# MCU009A_Xds100v2Emu.net
KiCad netlist of a schematic drawn in Altium Designer
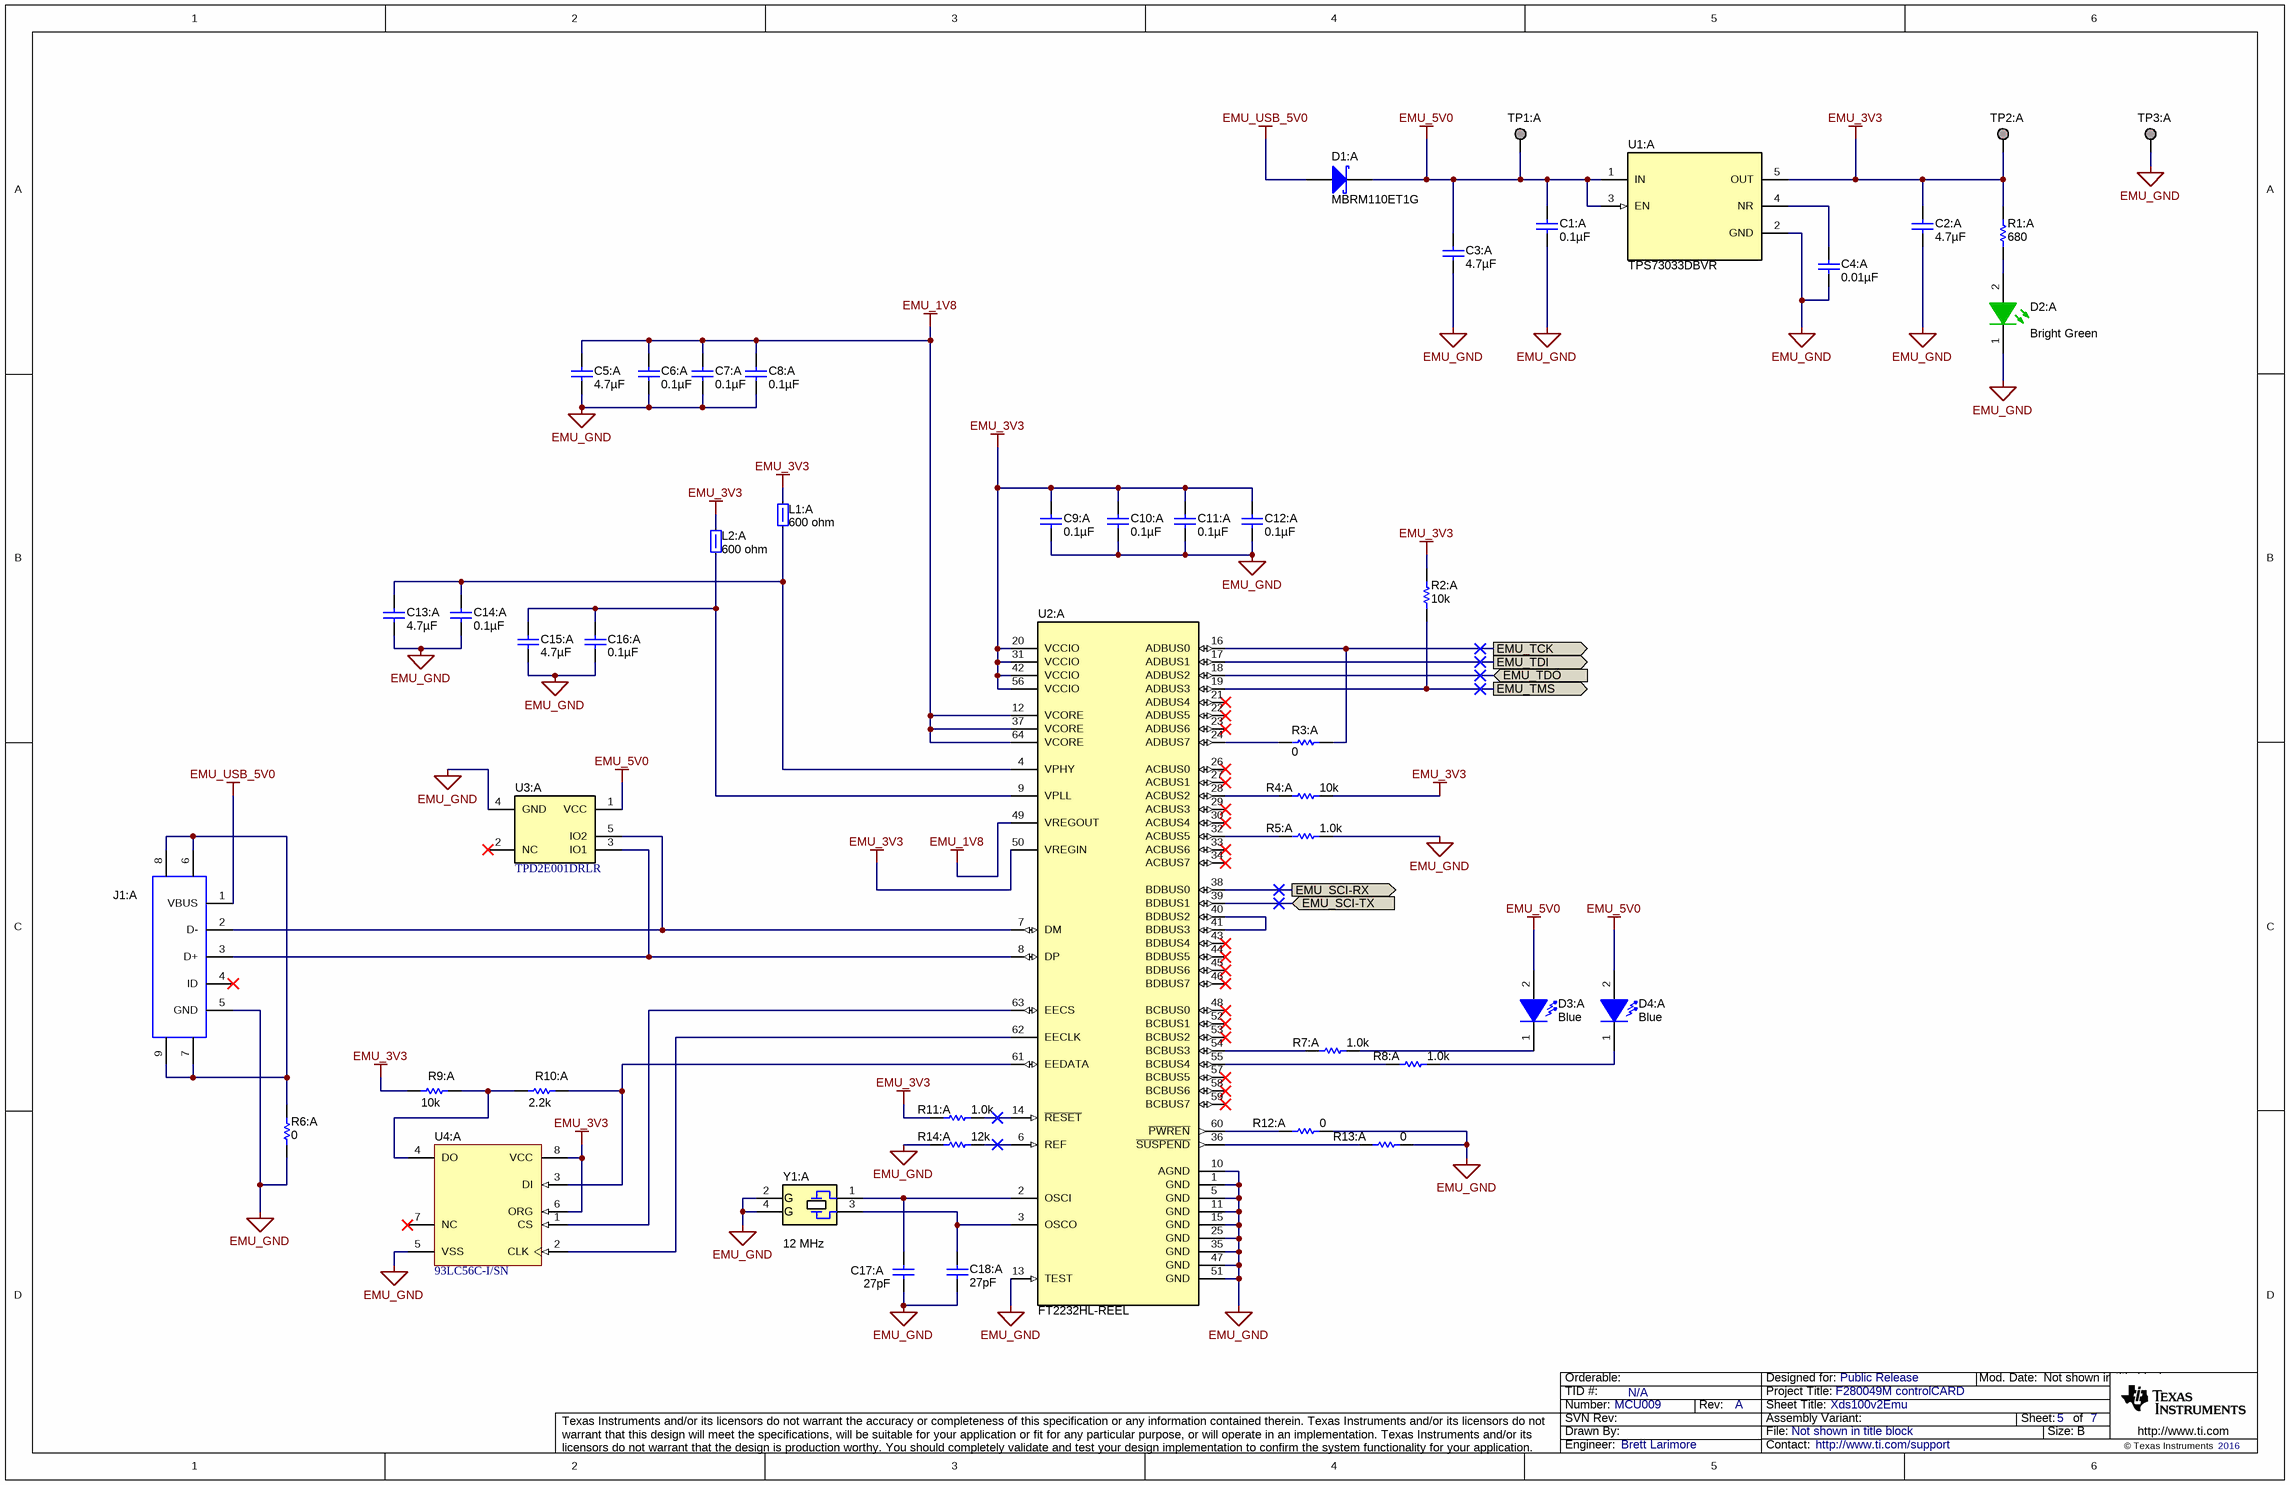
[diagram p0: MCU009A_Xds100v2Emu.SchDoc]

(export (version "E")
  (design (tool "Eeschema 10.0.6"))
  (components
    (comp (ref "C1:A")
      (value "GRM155R71A104KA01D")
      (footprint "0402")
      (description "CAP, CERM, 0.1 µF, 10 V, +/- 10%, X7R, 0402")
      (fields
        (field (name "VALUEDISPLAYED") "0.1µF")
        (field (name "MANUFACTURER") "MuRata")
        (field (name "PUBLISHER") "Texas Instruments")
      )
      (libsource (lib "Capacitor_Ceramic") (part "GRM155R71A104KA01D"))
    )
    (comp (ref "C2:A")
      (value "GRM188R60J475ME19D")
      (footprint "0603")
      (description "CAP, CERM, 4.7 µF, 6.3 V, +/- 20%, X5R, 0603")
      (fields
        (field (name "VALUEDISPLAYED") "4.7µF")
        (field (name "MANUFACTURER") "MuRata")
        (field (name "PUBLISHER") "Texas Instruments")
      )
      (libsource (lib "Capacitor_Ceramic") (part "GRM188R60J475ME19D"))
    )
    (comp (ref "C3:A")
      (value "GRM188R60J475ME19D")
      (footprint "0603")
      (description "CAP, CERM, 4.7 µF, 6.3 V, +/- 20%, X5R, 0603")
      (fields
        (field (name "VALUEDISPLAYED") "4.7µF")
        (field (name "MANUFACTURER") "MuRata")
        (field (name "PUBLISHER") "Texas Instruments")
      )
      (libsource (lib "Capacitor_Ceramic") (part "GRM188R60J475ME19D"))
    )
    (comp (ref "C4:A")
      (value "GRM155R71C103KA01D")
      (footprint "0402")
      (description "CAP, CERM, 0.01 µF, 16 V, +/- 10%, X7R, 0402")
      (fields
        (field (name "VALUEDISPLAYED") "0.01µF")
        (field (name "MANUFACTURER") "MuRata")
        (field (name "PUBLISHER") "Texas Instruments")
      )
      (libsource (lib "Capacitor_Ceramic") (part "GRM155R71C103KA01D"))
    )
    (comp (ref "C5:A")
      (value "GRM188R60J475ME19D")
      (footprint "0603")
      (description "CAP, CERM, 4.7 µF, 6.3 V, +/- 20%, X5R, 0603")
      (fields
        (field (name "VALUEDISPLAYED") "4.7µF")
        (field (name "MANUFACTURER") "MuRata")
        (field (name "PUBLISHER") "Texas Instruments")
      )
      (libsource (lib "Capacitor_Ceramic") (part "GRM188R60J475ME19D"))
    )
    (comp (ref "C6:A")
      (value "GRM155R71A104KA01D")
      (footprint "0402")
      (description "CAP, CERM, 0.1 µF, 10 V, +/- 10%, X7R, 0402")
      (fields
        (field (name "VALUEDISPLAYED") "0.1µF")
        (field (name "MANUFACTURER") "MuRata")
        (field (name "PUBLISHER") "Texas Instruments")
      )
      (libsource (lib "Capacitor_Ceramic") (part "GRM155R71A104KA01D"))
    )
    (comp (ref "C7:A")
      (value "GRM155R71A104KA01D")
      (footprint "0402")
      (description "CAP, CERM, 0.1 µF, 10 V, +/- 10%, X7R, 0402")
      (fields
        (field (name "VALUEDISPLAYED") "0.1µF")
        (field (name "MANUFACTURER") "MuRata")
        (field (name "PUBLISHER") "Texas Instruments")
      )
      (libsource (lib "Capacitor_Ceramic") (part "GRM155R71A104KA01D"))
    )
    (comp (ref "C8:A")
      (value "GRM155R71A104KA01D")
      (footprint "0402")
      (description "CAP, CERM, 0.1 µF, 10 V, +/- 10%, X7R, 0402")
      (fields
        (field (name "VALUEDISPLAYED") "0.1µF")
        (field (name "MANUFACTURER") "MuRata")
        (field (name "PUBLISHER") "Texas Instruments")
      )
      (libsource (lib "Capacitor_Ceramic") (part "GRM155R71A104KA01D"))
    )
    (comp (ref "C9:A")
      (value "GRM155R71A104KA01D")
      (footprint "0402")
      (description "CAP, CERM, 0.1 µF, 10 V, +/- 10%, X7R, 0402")
      (fields
        (field (name "VALUEDISPLAYED") "0.1µF")
        (field (name "MANUFACTURER") "MuRata")
        (field (name "PUBLISHER") "Texas Instruments")
      )
      (libsource (lib "Capacitor_Ceramic") (part "GRM155R71A104KA01D"))
    )
    (comp (ref "C10:A")
      (value "GRM155R71A104KA01D")
      (footprint "0402")
      (description "CAP, CERM, 0.1 µF, 10 V, +/- 10%, X7R, 0402")
      (fields
        (field (name "VALUEDISPLAYED") "0.1µF")
        (field (name "MANUFACTURER") "MuRata")
        (field (name "PUBLISHER") "Texas Instruments")
      )
      (libsource (lib "Capacitor_Ceramic") (part "GRM155R71A104KA01D"))
    )
    (comp (ref "C11:A")
      (value "GRM155R71A104KA01D")
      (footprint "0402")
      (description "CAP, CERM, 0.1 µF, 10 V, +/- 10%, X7R, 0402")
      (fields
        (field (name "VALUEDISPLAYED") "0.1µF")
        (field (name "MANUFACTURER") "MuRata")
        (field (name "PUBLISHER") "Texas Instruments")
      )
      (libsource (lib "Capacitor_Ceramic") (part "GRM155R71A104KA01D"))
    )
    (comp (ref "C12:A")
      (value "GRM155R71A104KA01D")
      (footprint "0402")
      (description "CAP, CERM, 0.1 µF, 10 V, +/- 10%, X7R, 0402")
      (fields
        (field (name "VALUEDISPLAYED") "0.1µF")
        (field (name "MANUFACTURER") "MuRata")
        (field (name "PUBLISHER") "Texas Instruments")
      )
      (libsource (lib "Capacitor_Ceramic") (part "GRM155R71A104KA01D"))
    )
    (comp (ref "C13:A")
      (value "GRM188R60J475ME19D")
      (footprint "0603")
      (description "CAP, CERM, 4.7 µF, 6.3 V, +/- 20%, X5R, 0603")
      (fields
        (field (name "VALUEDISPLAYED") "4.7µF")
        (field (name "MANUFACTURER") "MuRata")
        (field (name "PUBLISHER") "Texas Instruments")
      )
      (libsource (lib "Capacitor_Ceramic") (part "GRM188R60J475ME19D"))
    )
    (comp (ref "C14:A")
      (value "GRM155R71A104KA01D")
      (footprint "0402")
      (description "CAP, CERM, 0.1 µF, 10 V, +/- 10%, X7R, 0402")
      (fields
        (field (name "VALUEDISPLAYED") "0.1µF")
        (field (name "MANUFACTURER") "MuRata")
        (field (name "PUBLISHER") "Texas Instruments")
      )
      (libsource (lib "Capacitor_Ceramic") (part "GRM155R71A104KA01D"))
    )
    (comp (ref "C15:A")
      (value "GRM188R60J475ME19D")
      (footprint "0603")
      (description "CAP, CERM, 4.7 µF, 6.3 V, +/- 20%, X5R, 0603")
      (fields
        (field (name "VALUEDISPLAYED") "4.7µF")
        (field (name "MANUFACTURER") "MuRata")
        (field (name "PUBLISHER") "Texas Instruments")
      )
      (libsource (lib "Capacitor_Ceramic") (part "GRM188R60J475ME19D"))
    )
    (comp (ref "C16:A")
      (value "GRM155R71A104KA01D")
      (footprint "0402")
      (description "CAP, CERM, 0.1 µF, 10 V, +/- 10%, X7R, 0402")
      (fields
        (field (name "VALUEDISPLAYED") "0.1µF")
        (field (name "MANUFACTURER") "MuRata")
        (field (name "PUBLISHER") "Texas Instruments")
      )
      (libsource (lib "Capacitor_Ceramic") (part "GRM155R71A104KA01D"))
    )
    (comp (ref "C17:A")
      (value "GRM1555C1H270JA01D")
      (footprint "0402")
      (description "CAP, CERM, 27 pF, 50 V, +/- 5%, C0G/NP0, 0402")
      (fields
        (field (name "VALUEDISPLAYED") "27pF")
        (field (name "MANUFACTURER") "MuRata")
        (field (name "PUBLISHER") "Texas Instruments")
      )
      (libsource (lib "Capacitor_Ceramic") (part "GRM1555C1H270JA01D"))
    )
    (comp (ref "C18:A")
      (value "GRM1555C1H270JA01D")
      (footprint "0402")
      (description "CAP, CERM, 27 pF, 50 V, +/- 5%, C0G/NP0, 0402")
      (fields
        (field (name "VALUEDISPLAYED") "27pF")
        (field (name "MANUFACTURER") "MuRata")
        (field (name "PUBLISHER") "Texas Instruments")
      )
      (libsource (lib "Capacitor_Ceramic") (part "GRM1555C1H270JA01D"))
    )
    (comp (ref "D1:A")
      (value "MBRM110ET1G")
      (footprint "POWERMITE")
      (description "Diode, Schottky, 10 V, 1 A, AEC-Q101, POWERMITE")
      (fields (field (name "MANUFACTURER") "ON Semiconductor") (field (name "PUBLISHER") "Texas Instruments"))
      (libsource (lib "Diode") (part "MBRM110ET1G"))
    )
    (comp (ref "D2:A")
      (value "Bright Green")
      (footprint "WL-SMCW_Green_0805")
      (description "LED, Bright Green, SMD")
      (fields
        (field (name "PARTNUMBER") "150080VS75000")
        (field (name "MANUFACTURER") "Wurth Elektronik")
        (field (name "SYMBOLCREATOR") "Altium")
        (field (name "PUBLISHER") "Texas Instruments")
      )
      (libsource (lib "LED") (part "150080VS75000"))
    )
    (comp (ref "D3:A")
      (value "Blue")
      (footprint "WL-SMCW_Blue_0805")
      (description "LED, Blue, SMD")
      (fields
        (field (name "MANUFACTURER") "Wurth Elektronik")
        (field (name "PARTNUMBER") "150080BS75000")
        (field (name "PUBLISHER") "Texas Instruments")
      )
      (libsource (lib "LED") (part "150080BS75000"))
    )
    (comp (ref "D4:A")
      (value "Blue")
      (footprint "WL-SMCW_Blue_0805")
      (description "LED, Blue, SMD")
      (fields
        (field (name "MANUFACTURER") "Wurth Elektronik")
        (field (name "PARTNUMBER") "150080BS75000")
        (field (name "PUBLISHER") "Texas Instruments")
      )
      (libsource (lib "LED") (part "150080BS75000"))
    )
    (comp (ref "J1:A")
      (value "65100516121")
      (footprint "Wurth_65100516121")
      (description "Connector, Receptacle, USB Mini B 2.0, SMT")
      (fields
        (field (name "MANUFACTURER") "Wurth Elektronik")
        (field (name "SYMBOLCREATOR") "a0799628")
        (field (name "PUBLISHER") "Texas Instruments")
      )
      (libsource (lib "Connectors_Other") (part "65100516121"))
    )
    (comp (ref "L1:A")
      (value "600 ohm")
      (footprint "0805_HV")
      (description "Ferrite Bead, 600 ohm @ 100 MHz, 0.5 A, 0805")
      (fields
        (field (name "PARTNUMBER") "HZ0805E601R-10")
        (field (name "MANUFACTURER") "Laird-Signal Integrity Products")
        (field (name "PUBLISHER") "Texas Instruments")
      )
      (libsource (lib "FerriteBead") (part "HZ0805E601R-10"))
    )
    (comp (ref "L2:A")
      (value "600 ohm")
      (footprint "0805_HV")
      (description "Ferrite Bead, 600 ohm @ 100 MHz, 0.5 A, 0805")
      (fields
        (field (name "PARTNUMBER") "HZ0805E601R-10")
        (field (name "MANUFACTURER") "Laird-Signal Integrity Products")
        (field (name "PUBLISHER") "Texas Instruments")
      )
      (libsource (lib "FerriteBead") (part "HZ0805E601R-10"))
    )
    (comp (ref "R1:A")
      (value "CRCW0402680RJNED")
      (footprint "0402")
      (description "RES, 680, 5%, 0.063 W, 0402")
      (fields
        (field (name "VALUEDISPLAYED") "680")
        (field (name "MANUFACTURER") "Vishay-Dale")
        (field (name "PUBLISHER") "Texas Instruments")
      )
      (libsource (lib "Resistor_0402") (part "CRCW0402680RJNED"))
    )
    (comp (ref "R2:A")
      (value "CRCW040210K0JNED")
      (footprint "0402")
      (description "RES, 10 k, 5%, 0.063 W, 0402")
      (fields
        (field (name "VALUEDISPLAYED") "10k")
        (field (name "MANUFACTURER") "Vishay-Dale")
        (field (name "PUBLISHER") "Texas Instruments")
      )
      (libsource (lib "Resistor_0402") (part "CRCW040210K0JNED"))
    )
    (comp (ref "R3:A")
      (value "CRCW04020000Z0ED")
      (footprint "0402")
      (description "RES, 0, 5%, 0.063 W, 0402")
      (fields
        (field (name "VALUEDISPLAYED") "0")
        (field (name "MANUFACTURER") "Vishay-Dale")
        (field (name "PUBLISHER") "Texas Instruments")
      )
      (libsource (lib "Resistor_0402") (part "CRCW04020000Z0ED"))
    )
    (comp (ref "R4:A")
      (value "CRCW040210K0JNED")
      (footprint "0402")
      (description "RES, 10 k, 5%, 0.063 W, 0402")
      (fields
        (field (name "VALUEDISPLAYED") "10k")
        (field (name "MANUFACTURER") "Vishay-Dale")
        (field (name "PUBLISHER") "Texas Instruments")
      )
      (libsource (lib "Resistor_0402") (part "CRCW040210K0JNED"))
    )
    (comp (ref "R5:A")
      (value "CRCW04021K00JNED")
      (footprint "0402")
      (description "RES, 1.0 k, 5%, 0.063 W, 0402")
      (fields
        (field (name "VALUEDISPLAYED") "1.0k")
        (field (name "MANUFACTURER") "Vishay-Dale")
        (field (name "PUBLISHER") "Texas Instruments")
      )
      (libsource (lib "Resistor_0402") (part "CRCW04021K00JNED"))
    )
    (comp (ref "R6:A")
      (value "CRCW04020000Z0ED")
      (footprint "0402")
      (description "RES, 0, 5%, 0.063 W, 0402")
      (fields
        (field (name "VALUEDISPLAYED") "0")
        (field (name "MANUFACTURER") "Vishay-Dale")
        (field (name "PUBLISHER") "Texas Instruments")
      )
      (libsource (lib "Resistor_0402") (part "CRCW04020000Z0ED"))
    )
    (comp (ref "R7:A")
      (value "CRCW04021K00JNED")
      (footprint "0402")
      (description "RES, 1.0 k, 5%, 0.063 W, 0402")
      (fields
        (field (name "VALUEDISPLAYED") "1.0k")
        (field (name "MANUFACTURER") "Vishay-Dale")
        (field (name "PUBLISHER") "Texas Instruments")
      )
      (libsource (lib "Resistor_0402") (part "CRCW04021K00JNED"))
    )
    (comp (ref "R8:A")
      (value "CRCW04021K00JNED")
      (footprint "0402")
      (description "RES, 1.0 k, 5%, 0.063 W, 0402")
      (fields
        (field (name "VALUEDISPLAYED") "1.0k")
        (field (name "MANUFACTURER") "Vishay-Dale")
        (field (name "PUBLISHER") "Texas Instruments")
      )
      (libsource (lib "Resistor_0402") (part "CRCW04021K00JNED"))
    )
    (comp (ref "R9:A")
      (value "CRCW040210K0JNED")
      (footprint "0402")
      (description "RES, 10 k, 5%, 0.063 W, 0402")
      (fields
        (field (name "VALUEDISPLAYED") "10k")
        (field (name "MANUFACTURER") "Vishay-Dale")
        (field (name "PUBLISHER") "Texas Instruments")
      )
      (libsource (lib "Resistor_0402") (part "CRCW040210K0JNED"))
    )
    (comp (ref "R10:A")
      (value "CRCW04022K20JNED")
      (footprint "0402")
      (description "RES, 2.2 k, 5%, 0.063 W, 0402")
      (fields
        (field (name "VALUEDISPLAYED") "2.2k")
        (field (name "MANUFACTURER") "Vishay-Dale")
        (field (name "PUBLISHER") "Texas Instruments")
      )
      (libsource (lib "Resistor_0402") (part "CRCW04022K20JNED"))
    )
    (comp (ref "R11:A")
      (value "CRCW04021K00JNED")
      (footprint "0402")
      (description "RES, 1.0 k, 5%, 0.063 W, 0402")
      (fields
        (field (name "VALUEDISPLAYED") "1.0k")
        (field (name "MANUFACTURER") "Vishay-Dale")
        (field (name "PUBLISHER") "Texas Instruments")
      )
      (libsource (lib "Resistor_0402") (part "CRCW04021K00JNED"))
    )
    (comp (ref "R12:A")
      (value "CRCW04020000Z0ED")
      (footprint "0402")
      (description "RES, 0, 5%, 0.063 W, 0402")
      (fields
        (field (name "VALUEDISPLAYED") "0")
        (field (name "MANUFACTURER") "Vishay-Dale")
        (field (name "PUBLISHER") "Texas Instruments")
      )
      (libsource (lib "Resistor_0402") (part "CRCW04020000Z0ED"))
    )
    (comp (ref "R13:A")
      (value "CRCW04020000Z0ED")
      (footprint "0402")
      (description "RES, 0, 5%, 0.063 W, 0402")
      (fields
        (field (name "VALUEDISPLAYED") "0")
        (field (name "MANUFACTURER") "Vishay-Dale")
        (field (name "PUBLISHER") "Texas Instruments")
      )
      (libsource (lib "Resistor_0402") (part "CRCW04020000Z0ED"))
    )
    (comp (ref "R14:A")
      (value "CRCW040212K0JNED")
      (footprint "0402")
      (description "RES, 12 k, 5%, 0.063 W, 0402")
      (fields
        (field (name "VALUEDISPLAYED") "12k")
        (field (name "MANUFACTURER") "Vishay-Dale")
        (field (name "PUBLISHER") "Texas Instruments")
      )
      (libsource (lib "Resistor_0402") (part "CRCW040212K0JNED"))
    )
    (comp (ref "TP1:A")
      (value "TESTPOINT")
      (footprint "TP_50MIL-25MILHOLE")
      (description "TEST POINT.  No entry in BOM.")
      (fields (field (name "PUBLISHER") "Texas Instruments"))
      (libsource (lib "MiscParts") (part "TESTPOINT"))
    )
    (comp (ref "TP2:A")
      (value "TESTPOINT")
      (footprint "TP_50MIL-25MILHOLE")
      (description "TEST POINT.  No entry in BOM.")
      (fields (field (name "PUBLISHER") "Texas Instruments"))
      (libsource (lib "MiscParts") (part "TESTPOINT"))
    )
    (comp (ref "TP3:A")
      (value "TESTPOINT")
      (footprint "TP_50MIL-25MILHOLE")
      (description "TEST POINT.  No entry in BOM.")
      (fields (field (name "PUBLISHER") "Texas Instruments"))
      (libsource (lib "MiscParts") (part "TESTPOINT"))
    )
    (comp (ref "U1:A")
      (value "TPS73033DBVR")
      (footprint "DBV0005A_N")
      (description "Low-Noise, High PSRR, RF, 200-mA Low-Dropout Linear Regulator, DBV0005A (SOT-5)")
      (fields
        (field (name "ALTERNATE PARTNUMBER") "TPS73033DBVT")
        (field (name "MANUFACTURER") "Texas Instruments")
        (field (name "SYMBOLCREATOR") "a0411947")
        (field (name "PUBLISHER") "Texas Instruments")
      )
      (libsource (lib "TI_Pre_Release1") (part "TPS73033DBVR"))
    )
    (comp (ref "U2:A")
      (value "FT2232HL-REEL")
      (footprint "LQFP64_N")
      (description "Dual High Speed USB To Multipurpose UART/FIFO IC, LQFP-64")
      (fields
        (field (name "MANUFACTURER") "FTDI")
        (field (name "SYMBOLCREATOR") "Altium")
        (field (name "PUBLISHER") "Texas Instruments")
      )
      (libsource (lib "Other_IC") (part "FT2232HL-REEL"))
    )
    (comp (ref "U3:A")
      (value "TPD2E001DRLR")
      (footprint "DRL0005A")
      (fields
        (field (name "MANUFACTURER") "Texas Instruments")
        (field (name "ALTERNATE PARTNUMBER") "Equivalent")
      )
      (libsource (lib "TI Interface ESD EMI Protection") (part "TPD2E001DRLR"))
    )
    (comp (ref "U4:A")
      (value "93LC56C-I/SN")
      (footprint "SOIC-8")
      (description "2K Microwire Compatible Serial EEPROM, SOIC-8")
      (fields
        (field (name "MANUFACTURER") "Microchip")
        (field (name "SYMBOLCREATOR") "a0411947")
        (field (name "PUBLISHER") "Texas Instruments")
      )
      (libsource (lib "Other_IC") (part "93LC56C-I/SN"))
    )
    (comp (ref "Y1:A")
      (value "ECS-120-20-30B-TR")
      (footprint "ECS_ECX-53B")
      (description "Crystal, 12MHz, 20pF, SMD")
      (fields
        (field (name "FREQUENCY") "12 MHz")
        (field (name "MANUFACTURER") "ECS Inc.")
        (field (name "SYMBOLCREATOR") "a0411947")
        (field (name "PUBLISHER") "Texas Instruments")
      )
      (libsource (lib "Oscillators") (part "ECS-120-20-30B-TR"))
    )
  )
  (nets
    (net (code "1") (name "/EMU_SCI-RX") (class "Default")
      (node (ref "U2:A") (pin "38") (pinfunction "BDBUS0_38") (pintype "bidirectional"))
    )
    (net (code "2") (name "/EMU_SCI-TX") (class "Default")
      (node (ref "U2:A") (pin "39") (pinfunction "BDBUS1_39") (pintype "bidirectional"))
    )
    (net (code "3") (name "/EMU_TCK") (class "Default")
      (node (ref "R3:A") (pin "1") (pinfunction "1_1") (pintype "passive"))
      (node (ref "U2:A") (pin "16") (pinfunction "ADBUS0_16") (pintype "bidirectional"))
    )
    (net (code "4") (name "/EMU_TDI") (class "Default")
      (node (ref "U2:A") (pin "17") (pinfunction "ADBUS1_17") (pintype "bidirectional"))
    )
    (net (code "5") (name "/EMU_TDO") (class "Default")
      (node (ref "U2:A") (pin "18") (pinfunction "ADBUS2_18") (pintype "bidirectional"))
    )
    (net (code "6") (name "/EMU_TMS") (class "Default")
      (node (ref "R2:A") (pin "1") (pinfunction "1_1") (pintype "passive"))
      (node (ref "U2:A") (pin "19") (pinfunction "ADBUS3_19") (pintype "bidirectional"))
    )
    (net (code "7") (name "EMU_1V8") (class "Default")
      (node (ref "C5:A") (pin "2") (pinfunction "2_2") (pintype "passive"))
      (node (ref "C6:A") (pin "2") (pinfunction "2_2") (pintype "passive"))
      (node (ref "C7:A") (pin "2") (pinfunction "2_2") (pintype "passive"))
      (node (ref "C8:A") (pin "2") (pinfunction "2_2") (pintype "passive"))
      (node (ref "U2:A") (pin "12") (pinfunction "VCORE_12") (pintype "power_in"))
      (node (ref "U2:A") (pin "37") (pinfunction "VCORE_37") (pintype "power_in"))
      (node (ref "U2:A") (pin "49") (pinfunction "VREGOUT_49") (pintype "power_in"))
      (node (ref "U2:A") (pin "64") (pinfunction "VCORE_64") (pintype "power_in"))
    )
    (net (code "8") (name "EMU_3V3") (class "Default")
      (node (ref "C10:A") (pin "2") (pinfunction "2_2") (pintype "passive"))
      (node (ref "C11:A") (pin "2") (pinfunction "2_2") (pintype "passive"))
      (node (ref "C12:A") (pin "2") (pinfunction "2_2") (pintype "passive"))
      (node (ref "C2:A") (pin "1") (pinfunction "1_1") (pintype "passive"))
      (node (ref "C9:A") (pin "2") (pinfunction "2_2") (pintype "passive"))
      (node (ref "L1:A") (pin "2") (pinfunction "2_2") (pintype "passive"))
      (node (ref "L2:A") (pin "2") (pinfunction "2_2") (pintype "passive"))
      (node (ref "R11:A") (pin "1") (pinfunction "1_1") (pintype "passive"))
      (node (ref "R1:A") (pin "1") (pinfunction "1_1") (pintype "passive"))
      (node (ref "R2:A") (pin "2") (pinfunction "2_2") (pintype "passive"))
      (node (ref "R4:A") (pin "2") (pinfunction "2_2") (pintype "passive"))
      (node (ref "R9:A") (pin "1") (pinfunction "1_1") (pintype "passive"))
      (node (ref "TP2:A") (pin "1") (pintype "passive"))
      (node (ref "U1:A") (pin "5") (pinfunction "OUT_5") (pintype "power_in"))
      (node (ref "U2:A") (pin "20") (pinfunction "VCCIO_20") (pintype "power_in"))
      (node (ref "U2:A") (pin "31") (pinfunction "VCCIO_31") (pintype "power_in"))
      (node (ref "U2:A") (pin "42") (pinfunction "VCCIO_42") (pintype "power_in"))
      (node (ref "U2:A") (pin "50") (pinfunction "VREGIN_50") (pintype "power_in"))
      (node (ref "U2:A") (pin "56") (pinfunction "VCCIO_56") (pintype "power_in"))
      (node (ref "U4:A") (pin "6") (pinfunction "ORG_6") (pintype "input"))
      (node (ref "U4:A") (pin "8") (pinfunction "VCC_8") (pintype "power_in"))
    )
    (net (code "9") (name "EMU_5V0") (class "Default")
      (node (ref "C1:A") (pin "2") (pinfunction "2_2") (pintype "passive"))
      (node (ref "C3:A") (pin "1") (pinfunction "1_1") (pintype "passive"))
      (node (ref "D1:A") (pin "1") (pinfunction "K_1") (pintype "passive"))
      (node (ref "D3:A") (pin "2") (pinfunction "A_2") (pintype "passive"))
      (node (ref "D4:A") (pin "2") (pinfunction "A_2") (pintype "passive"))
      (node (ref "TP1:A") (pin "1") (pintype "passive"))
      (node (ref "U1:A") (pin "1") (pinfunction "IN_1") (pintype "power_in"))
      (node (ref "U1:A") (pin "3") (pinfunction "EN_3") (pintype "input"))
      (node (ref "U3:A") (pin "1") (pinfunction "VCC_1") (pintype "power_in"))
    )
    (net (code "10") (name "EMU_GND") (class "Default")
      (node (ref "C10:A") (pin "1") (pinfunction "1_1") (pintype "passive"))
      (node (ref "C11:A") (pin "1") (pinfunction "1_1") (pintype "passive"))
      (node (ref "C12:A") (pin "1") (pinfunction "1_1") (pintype "passive"))
      (node (ref "C13:A") (pin "2") (pinfunction "2_2") (pintype "passive"))
      (node (ref "C14:A") (pin "1") (pinfunction "1_1") (pintype "passive"))
      (node (ref "C15:A") (pin "2") (pinfunction "2_2") (pintype "passive"))
      (node (ref "C16:A") (pin "1") (pinfunction "1_1") (pintype "passive"))
      (node (ref "C17:A") (pin "1") (pinfunction "1_1") (pintype "passive"))
      (node (ref "C18:A") (pin "1") (pinfunction "1_1") (pintype "passive"))
      (node (ref "C1:A") (pin "1") (pinfunction "1_1") (pintype "passive"))
      (node (ref "C2:A") (pin "2") (pinfunction "2_2") (pintype "passive"))
      (node (ref "C3:A") (pin "2") (pinfunction "2_2") (pintype "passive"))
      (node (ref "C4:A") (pin "1") (pinfunction "1_1") (pintype "passive"))
      (node (ref "C5:A") (pin "1") (pinfunction "1_1") (pintype "passive"))
      (node (ref "C6:A") (pin "1") (pinfunction "1_1") (pintype "passive"))
      (node (ref "C7:A") (pin "1") (pinfunction "1_1") (pintype "passive"))
      (node (ref "C8:A") (pin "1") (pinfunction "1_1") (pintype "passive"))
      (node (ref "C9:A") (pin "1") (pinfunction "1_1") (pintype "passive"))
      (node (ref "D2:A") (pin "1") (pinfunction "K_1") (pintype "passive"))
      (node (ref "J1:A") (pin "5") (pinfunction "GND_5") (pintype "passive"))
      (node (ref "R12:A") (pin "1") (pinfunction "1_1") (pintype "passive"))
      (node (ref "R13:A") (pin "1") (pinfunction "1_1") (pintype "passive"))
      (node (ref "R14:A") (pin "1") (pinfunction "1_1") (pintype "passive"))
      (node (ref "R5:A") (pin "2") (pinfunction "2_2") (pintype "passive"))
      (node (ref "R6:A") (pin "2") (pinfunction "2_2") (pintype "passive"))
      (node (ref "TP3:A") (pin "1") (pintype "passive"))
      (node (ref "U1:A") (pin "2") (pinfunction "GND_2") (pintype "power_in"))
      (node (ref "U2:A") (pin "1") (pinfunction "GND_1") (pintype "power_in"))
      (node (ref "U2:A") (pin "10") (pinfunction "AGND_10") (pintype "power_in"))
      (node (ref "U2:A") (pin "11") (pinfunction "GND_11") (pintype "power_in"))
      (node (ref "U2:A") (pin "13") (pinfunction "TEST_13") (pintype "input"))
      (node (ref "U2:A") (pin "15") (pinfunction "GND_15") (pintype "power_in"))
      (node (ref "U2:A") (pin "25") (pinfunction "GND_25") (pintype "power_in"))
      (node (ref "U2:A") (pin "35") (pinfunction "GND_35") (pintype "power_in"))
      (node (ref "U2:A") (pin "47") (pinfunction "GND_47") (pintype "power_in"))
      (node (ref "U2:A") (pin "5") (pinfunction "GND_5") (pintype "power_in"))
      (node (ref "U2:A") (pin "51") (pinfunction "GND_51") (pintype "power_in"))
      (node (ref "U3:A") (pin "4") (pinfunction "GND_4") (pintype "power_in"))
      (node (ref "U4:A") (pin "5") (pinfunction "VSS_5") (pintype "power_in"))
      (node (ref "Y1:A") (pin "2") (pinfunction "GND_2") (pintype "power_in"))
      (node (ref "Y1:A") (pin "4") (pinfunction "GND_4") (pintype "power_in"))
    )
    (net (code "11") (name "EMU_USB_5V0") (class "Default")
      (node (ref "D1:A") (pin "2") (pinfunction "A_2") (pintype "passive"))
      (node (ref "J1:A") (pin "1") (pinfunction "VBUS_1") (pintype "passive"))
    )
    (net (code "12") (name "Net-(D2:A-A)") (class "Default")
      (node (ref "D2:A") (pin "2") (pinfunction "A_2") (pintype "passive"))
      (node (ref "R1:A") (pin "2") (pinfunction "2_2") (pintype "passive"))
    )
    (net (code "13") (name "Net-(D3:A-K)") (class "Default")
      (node (ref "D3:A") (pin "1") (pinfunction "K_1") (pintype "passive"))
      (node (ref "R7:A") (pin "2") (pinfunction "2_2") (pintype "passive"))
    )
    (net (code "14") (name "Net-(D4:A-K)") (class "Default")
      (node (ref "D4:A") (pin "1") (pinfunction "K_1") (pintype "passive"))
      (node (ref "R8:A") (pin "2") (pinfunction "2_2") (pintype "passive"))
    )
    (net (code "15") (name "Net-(J1:A-D+)") (class "Default")
      (node (ref "J1:A") (pin "3") (pinfunction "D+_3") (pintype "passive"))
      (node (ref "U2:A") (pin "8") (pinfunction "DP_8") (pintype "bidirectional"))
      (node (ref "U3:A") (pin "3") (pinfunction "IO1_3") (pintype "passive"))
    )
    (net (code "16") (name "Net-(J1:A-D-)") (class "Default")
      (node (ref "J1:A") (pin "2") (pinfunction "D-_2") (pintype "passive"))
      (node (ref "U2:A") (pin "7") (pinfunction "DM_7") (pintype "bidirectional"))
      (node (ref "U3:A") (pin "5") (pinfunction "IO2_5") (pintype "passive"))
    )
    (net (code "17") (name "Net-(J1:A-Pad6)") (class "Default")
      (node (ref "J1:A") (pin "6") (pinfunction "6_6") (pintype "passive"))
      (node (ref "J1:A") (pin "7") (pinfunction "7_7") (pintype "passive"))
      (node (ref "J1:A") (pin "8") (pinfunction "8_8") (pintype "passive"))
      (node (ref "J1:A") (pin "9") (pinfunction "9_9") (pintype "passive"))
      (node (ref "R6:A") (pin "1") (pinfunction "1_1") (pintype "passive"))
    )
    (net (code "18") (name "Net-(U1:A-NR)") (class "Default")
      (node (ref "C4:A") (pin "2") (pinfunction "2_2") (pintype "passive"))
      (node (ref "U1:A") (pin "4") (pinfunction "NR_4") (pintype "passive"))
    )
    (net (code "19") (name "Net-(U2:A-ACBUS2)") (class "Default")
      (node (ref "R4:A") (pin "1") (pinfunction "1_1") (pintype "passive"))
      (node (ref "U2:A") (pin "28") (pinfunction "ACBUS2_28") (pintype "bidirectional"))
    )
    (net (code "20") (name "Net-(U2:A-ACBUS5)") (class "Default")
      (node (ref "R5:A") (pin "1") (pinfunction "1_1") (pintype "passive"))
      (node (ref "U2:A") (pin "32") (pinfunction "ACBUS5_32") (pintype "bidirectional"))
    )
    (net (code "21") (name "Net-(U2:A-ADBUS7)") (class "Default")
      (node (ref "R3:A") (pin "2") (pinfunction "2_2") (pintype "passive"))
      (node (ref "U2:A") (pin "24") (pinfunction "ADBUS7_24") (pintype "bidirectional"))
    )
    (net (code "22") (name "Net-(U2:A-BCBUS3)") (class "Default")
      (node (ref "R7:A") (pin "1") (pinfunction "1_1") (pintype "passive"))
      (node (ref "U2:A") (pin "54") (pinfunction "BCBUS3_54") (pintype "bidirectional"))
    )
    (net (code "23") (name "Net-(U2:A-BCBUS4)") (class "Default")
      (node (ref "R8:A") (pin "1") (pinfunction "1_1") (pintype "passive"))
      (node (ref "U2:A") (pin "55") (pinfunction "BCBUS4_55") (pintype "bidirectional"))
    )
    (net (code "24") (name "Net-(U2:A-BDBUS2)") (class "Default")
      (node (ref "U2:A") (pin "40") (pinfunction "BDBUS2_40") (pintype "bidirectional"))
      (node (ref "U2:A") (pin "41") (pinfunction "BDBUS3_41") (pintype "bidirectional"))
    )
    (net (code "25") (name "Net-(U2:A-EECLK)") (class "Default")
      (node (ref "U2:A") (pin "62") (pinfunction "EECLK_62") (pintype "tri_state"))
      (node (ref "U4:A") (pin "2") (pinfunction "CLK_2") (pintype "input"))
    )
    (net (code "26") (name "Net-(U2:A-EECS)") (class "Default")
      (node (ref "U2:A") (pin "63") (pinfunction "EECS_63") (pintype "bidirectional"))
      (node (ref "U4:A") (pin "1") (pinfunction "CS_1") (pintype "input"))
    )
    (net (code "27") (name "Net-(U2:A-EEDATA)") (class "Default")
      (node (ref "R10:A") (pin "2") (pinfunction "2_2") (pintype "passive"))
      (node (ref "U2:A") (pin "61") (pinfunction "EEDATA_61") (pintype "bidirectional"))
      (node (ref "U4:A") (pin "3") (pinfunction "DI_3") (pintype "input"))
    )
    (net (code "28") (name "Net-(U2:A-OSCI)") (class "Default")
      (node (ref "C17:A") (pin "2") (pinfunction "2_2") (pintype "passive"))
      (node (ref "U2:A") (pin "2") (pinfunction "OSCI_2") (pintype "passive"))
      (node (ref "Y1:A") (pin "1") (pinfunction "1_1") (pintype "passive"))
    )
    (net (code "29") (name "Net-(U2:A-OSCO)") (class "Default")
      (node (ref "C18:A") (pin "2") (pinfunction "2_2") (pintype "passive"))
      (node (ref "U2:A") (pin "3") (pinfunction "OSCO_3") (pintype "passive"))
      (node (ref "Y1:A") (pin "3") (pinfunction "3_3") (pintype "passive"))
    )
    (net (code "30") (name "Net-(U2:A-REF)") (class "Default")
      (node (ref "R14:A") (pin "2") (pinfunction "2_2") (pintype "passive"))
      (node (ref "U2:A") (pin "6") (pinfunction "REF_6") (pintype "input"))
    )
    (net (code "31") (name "Net-(U2:A-VPHY)") (class "Default")
      (node (ref "C13:A") (pin "1") (pinfunction "1_1") (pintype "passive"))
      (node (ref "C14:A") (pin "2") (pinfunction "2_2") (pintype "passive"))
      (node (ref "L1:A") (pin "1") (pinfunction "1_1") (pintype "passive"))
      (node (ref "U2:A") (pin "4") (pinfunction "VPHY_4") (pintype "power_in"))
    )
    (net (code "32") (name "Net-(U2:A-VPLL)") (class "Default")
      (node (ref "C15:A") (pin "1") (pinfunction "1_1") (pintype "passive"))
      (node (ref "C16:A") (pin "2") (pinfunction "2_2") (pintype "passive"))
      (node (ref "L2:A") (pin "1") (pinfunction "1_1") (pintype "passive"))
      (node (ref "U2:A") (pin "9") (pinfunction "VPLL_9") (pintype "power_in"))
    )
    (net (code "33") (name "Net-(U2:A-~{PWREN})") (class "Default")
      (node (ref "R12:A") (pin "2") (pinfunction "2_2") (pintype "passive"))
      (node (ref "U2:A") (pin "60") (pinfunction "~{PWREN}_60") (pintype "output"))
    )
    (net (code "34") (name "Net-(U2:A-~{RESET})") (class "Default")
      (node (ref "R11:A") (pin "2") (pinfunction "2_2") (pintype "passive"))
      (node (ref "U2:A") (pin "14") (pinfunction "~{RESET}_14") (pintype "input"))
    )
    (net (code "35") (name "Net-(U2:A-~{SUSPEND})") (class "Default")
      (node (ref "R13:A") (pin "2") (pinfunction "2_2") (pintype "passive"))
      (node (ref "U2:A") (pin "36") (pinfunction "~{SUSPEND}_36") (pintype "output"))
    )
    (net (code "36") (name "Net-(U4:A-DO)") (class "Default")
      (node (ref "R10:A") (pin "1") (pinfunction "1_1") (pintype "passive"))
      (node (ref "R9:A") (pin "2") (pinfunction "2_2") (pintype "passive"))
      (node (ref "U4:A") (pin "4") (pinfunction "DO_4") (pintype "tri_state"))
    )
    (net (code "37") (name "unconnected-(J1:A-ID-Pad4)") (class "Default")
      (node (ref "J1:A") (pin "4") (pinfunction "ID_4") (pintype "passive+no_connect"))
    )
    (net (code "38") (name "unconnected-(U2:A-ACBUS0-Pad26)") (class "Default")
      (node (ref "U2:A") (pin "26") (pinfunction "ACBUS0_26") (pintype "bidirectional+no_connect"))
    )
    (net (code "39") (name "unconnected-(U2:A-ACBUS1-Pad27)") (class "Default")
      (node (ref "U2:A") (pin "27") (pinfunction "ACBUS1_27") (pintype "bidirectional+no_connect"))
    )
    (net (code "40") (name "unconnected-(U2:A-ACBUS3-Pad29)") (class "Default")
      (node (ref "U2:A") (pin "29") (pinfunction "ACBUS3_29") (pintype "bidirectional+no_connect"))
    )
    (net (code "41") (name "unconnected-(U2:A-ACBUS4-Pad30)") (class "Default")
      (node (ref "U2:A") (pin "30") (pinfunction "ACBUS4_30") (pintype "bidirectional+no_connect"))
    )
    (net (code "42") (name "unconnected-(U2:A-ACBUS6-Pad33)") (class "Default")
      (node (ref "U2:A") (pin "33") (pinfunction "ACBUS6_33") (pintype "bidirectional+no_connect"))
    )
    (net (code "43") (name "unconnected-(U2:A-ACBUS7-Pad34)") (class "Default")
      (node (ref "U2:A") (pin "34") (pinfunction "ACBUS7_34") (pintype "bidirectional+no_connect"))
    )
    (net (code "44") (name "unconnected-(U2:A-ADBUS4-Pad21)") (class "Default")
      (node (ref "U2:A") (pin "21") (pinfunction "ADBUS4_21") (pintype "bidirectional+no_connect"))
    )
    (net (code "45") (name "unconnected-(U2:A-ADBUS5-Pad22)") (class "Default")
      (node (ref "U2:A") (pin "22") (pinfunction "ADBUS5_22") (pintype "bidirectional+no_connect"))
    )
    (net (code "46") (name "unconnected-(U2:A-ADBUS6-Pad23)") (class "Default")
      (node (ref "U2:A") (pin "23") (pinfunction "ADBUS6_23") (pintype "bidirectional+no_connect"))
    )
    (net (code "47") (name "unconnected-(U2:A-BCBUS0-Pad48)") (class "Default")
      (node (ref "U2:A") (pin "48") (pinfunction "BCBUS0_48") (pintype "bidirectional+no_connect"))
    )
    (net (code "48") (name "unconnected-(U2:A-BCBUS1-Pad52)") (class "Default")
      (node (ref "U2:A") (pin "52") (pinfunction "BCBUS1_52") (pintype "bidirectional+no_connect"))
    )
    (net (code "49") (name "unconnected-(U2:A-BCBUS2-Pad53)") (class "Default")
      (node (ref "U2:A") (pin "53") (pinfunction "BCBUS2_53") (pintype "bidirectional+no_connect"))
    )
    (net (code "50") (name "unconnected-(U2:A-BCBUS5-Pad57)") (class "Default")
      (node (ref "U2:A") (pin "57") (pinfunction "BCBUS5_57") (pintype "bidirectional+no_connect"))
    )
    (net (code "51") (name "unconnected-(U2:A-BCBUS6-Pad58)") (class "Default")
      (node (ref "U2:A") (pin "58") (pinfunction "BCBUS6_58") (pintype "bidirectional+no_connect"))
    )
    (net (code "52") (name "unconnected-(U2:A-BCBUS7-Pad59)") (class "Default")
      (node (ref "U2:A") (pin "59") (pinfunction "BCBUS7_59") (pintype "bidirectional+no_connect"))
    )
    (net (code "53") (name "unconnected-(U2:A-BDBUS4-Pad43)") (class "Default")
      (node (ref "U2:A") (pin "43") (pinfunction "BDBUS4_43") (pintype "bidirectional+no_connect"))
    )
    (net (code "54") (name "unconnected-(U2:A-BDBUS5-Pad44)") (class "Default")
      (node (ref "U2:A") (pin "44") (pinfunction "BDBUS5_44") (pintype "bidirectional+no_connect"))
    )
    (net (code "55") (name "unconnected-(U2:A-BDBUS6-Pad45)") (class "Default")
      (node (ref "U2:A") (pin "45") (pinfunction "BDBUS6_45") (pintype "bidirectional+no_connect"))
    )
    (net (code "56") (name "unconnected-(U2:A-BDBUS7-Pad46)") (class "Default")
      (node (ref "U2:A") (pin "46") (pinfunction "BDBUS7_46") (pintype "bidirectional+no_connect"))
    )
    (net (code "57") (name "unconnected-(U3:A-NC-Pad2)") (class "Default")
      (node (ref "U3:A") (pin "2") (pinfunction "NC_2") (pintype "passive+no_connect"))
    )
    (net (code "58") (name "unconnected-(U4:A-NC-Pad7)") (class "Default")
      (node (ref "U4:A") (pin "7") (pinfunction "NC_7") (pintype "passive+no_connect"))
    )
  )
)
